# Connector.net
KiCad netlist of a schematic drawn in Altium Designer
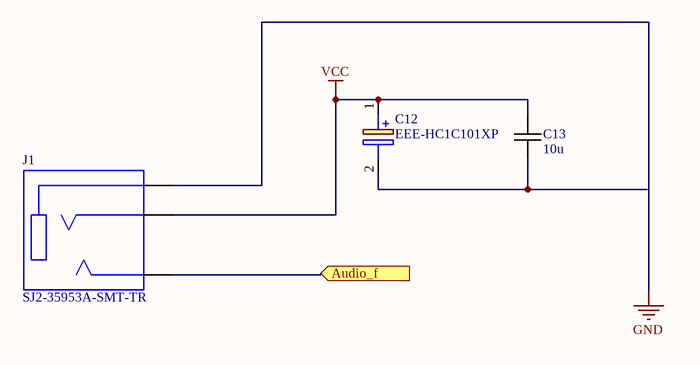
[diagram p0: Connector.SchDoc]

(export (version "E")
  (design (tool "Eeschema 10.0.6"))
  (components
    (comp (ref "C12")
      (value "EEE-HC1C101XP")
      (footprint "CAPAE660X800N")
      (description "Capacitor Polarised")
      (fields (field (name "MOUSER PART NUMBER") "667-EEE-HC1C101XP"))
      (libsource (lib "PMOD") (part "EEE-HC1C101XP"))
    )
    (comp (ref "C13")
      (value "10u")
      (footprint "0805C-GENERIC")
      (description "GENERIC CAPACITOR NON POLARISED0603")
      (libsource (lib "vh_altium_library") (part "C0805-GENERIC"))
    )
    (comp (ref "J1")
      (value "SJ2-35953A-SMT-TR")
      (footprint "CUI_SJ2-35953A-SMT-TR")
      (description "3.5 mm, Stereo, Right Angle, Surface Mount _SMT_, Audio Jack Connector")
      (fields (field (name "MF") "CUI Devices"))
      (libsource (lib "SJ2-35953A-SMT-TR") (part "SJ2-35953A-SMT-TR"))
    )
  )
  (nets
    (net (code "1") (name "/Audio_f") (class "Default")
      (node (ref "J1") (pin "2") (pinfunction "TIP_2") (pintype "passive"))
    )
    (net (code "2") (name "GND") (class "Default")
      (node (ref "J1") (pin "1") (pinfunction "SLEEVE_1") (pintype "passive"))
    )
    (net (code "3") (name "Net-(C12--)") (class "Default")
      (node (ref "C12") (pin "2") (pinfunction "-_2") (pintype "passive"))
      (node (ref "C13") (pin "2") (pintype "passive"))
    )
    (net (code "4") (name "VCC") (class "Default")
      (node (ref "C12") (pin "1") (pinfunction "+_1") (pintype "passive"))
      (node (ref "C13") (pin "1") (pintype "passive"))
      (node (ref "J1") (pin "3") (pinfunction "RING1_3") (pintype "passive"))
    )
  )
)
